# disarm_it_schem.net
KiCad netlist of a schematic drawn in Altium Designer
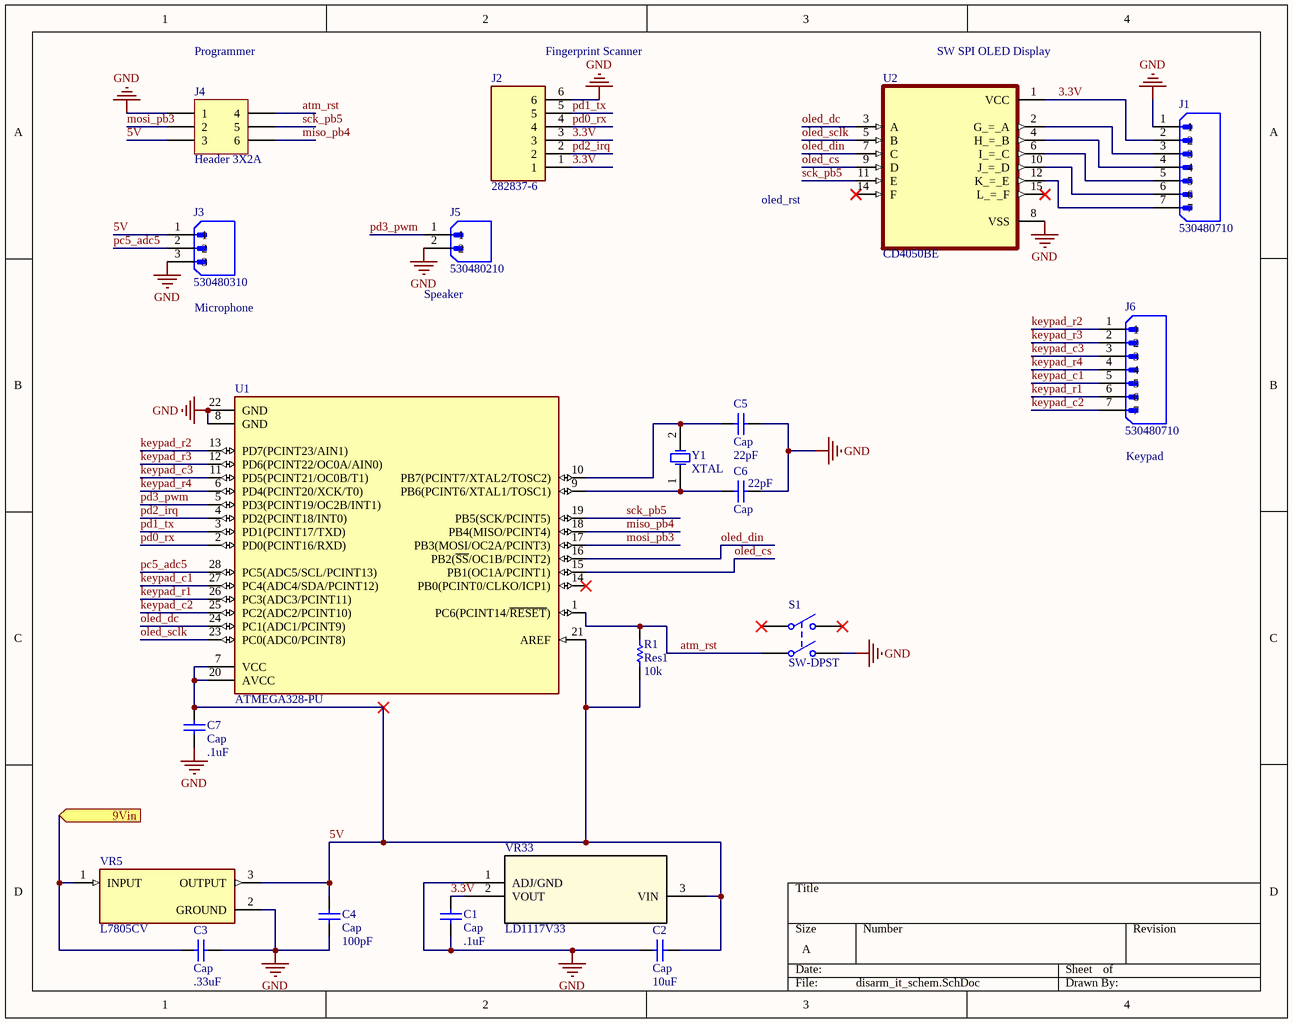
[diagram p0: disarm_it_schem.SchDoc]

(export (version "E")
  (design (tool "Eeschema 10.0.6"))
  (components
    (comp (ref "C1")
      (value "Cap")
      (footprint "RAD-0.3")
      (description "Capacitor")
      (fields (field (name "ALTIUM_VALUE") ".1uF") (field (name "PUBLISHER") "Altium Limited"))
      (libsource (lib "Miscellaneous Devices") (part "Cap"))
    )
    (comp (ref "C2")
      (value "Cap")
      (footprint "RAD-0.3")
      (description "Capacitor")
      (fields (field (name "ALTIUM_VALUE") "10uF") (field (name "PUBLISHER") "Altium Limited"))
      (libsource (lib "Miscellaneous Devices") (part "Cap"))
    )
    (comp (ref "C3")
      (value "Cap")
      (footprint "RAD-0.3")
      (description "Capacitor")
      (fields (field (name "ALTIUM_VALUE") ".33uF") (field (name "PUBLISHER") "Altium Limited"))
      (libsource (lib "Miscellaneous Devices") (part "Cap"))
    )
    (comp (ref "C4")
      (value "Cap")
      (footprint "RAD-0.3")
      (description "Capacitor")
      (fields (field (name "ALTIUM_VALUE") "100pF") (field (name "PUBLISHER") "Altium Limited"))
      (libsource (lib "Miscellaneous Devices") (part "Cap"))
    )
    (comp (ref "C5")
      (value "Cap")
      (footprint "RAD-0.3")
      (description "Capacitor")
      (fields (field (name "ALTIUM_VALUE") "22pF") (field (name "PUBLISHER") "Altium Limited"))
      (libsource (lib "Miscellaneous Devices") (part "Cap"))
    )
    (comp (ref "C6")
      (value "Cap")
      (footprint "RAD-0.3")
      (description "Capacitor")
      (fields (field (name "ALTIUM_VALUE") "22pF") (field (name "PUBLISHER") "Altium Limited"))
      (libsource (lib "Miscellaneous Devices") (part "Cap"))
    )
    (comp (ref "C7")
      (value "Cap")
      (footprint "RAD-0.3")
      (description "Capacitor")
      (fields (field (name "ALTIUM_VALUE") ".1uF") (field (name "PUBLISHER") "Altium Limited"))
      (libsource (lib "Miscellaneous Devices") (part "Cap"))
    )
    (comp (ref "J1")
      (value "530480710")
      (footprint "MOLEX_530480710")
      (libsource (lib "530480710") (part "530480710"))
    )
    (comp (ref "J2")
      (value "282837-6")
      (footprint "TE_282837-6")
      (description "Conn Terminal Block F 6 POS 5.08mm Solder ST Thru-Hole 13.5A/Contact")
      (fields (field (name "MF") "TE Connectivity"))
      (libsource (lib "282837-6") (part "282837-6"))
    )
    (comp (ref "J3")
      (value "530480310")
      (footprint "MOLEX_530480310")
      (description "Conn Shrouded Header (4 Sides) HDR 3 POS 1.25mm Solder RA Side Entry Thru-Hole PicoBladeâ„¢ Tray")
      (fields (field (name "MF") "Molex") (field (name "DIGI-KEY_PART_NUMBER") "2266-53048-0310-ND"))
      (libsource (lib "530480310") (part "530480310"))
    )
    (comp (ref "J4")
      (value "Header 3X2A")
      (footprint "HDR2X3_CEN")
      (description "Header, 3-Pin, Dual row")
      (fields (field (name "PUBLISHER") "Altium Limited"))
      (libsource (lib "Miscellaneous Connectors") (part "Header 3X2A"))
    )
    (comp (ref "J5")
      (value "530480210")
      (footprint "MOLEX_530480210")
      (description "Conn Shrouded Header (4 Sides) HDR 2 POS 1.25mm Solder RA Side Entry Thru-Hole PicoBladeâ„¢ Tray")
      (fields (field (name "MF") "Molex") (field (name "DIGI-KEY_PART_NUMBER") "2266-53048-0210-ND"))
      (libsource (lib "530480210") (part "530480210"))
    )
    (comp (ref "J6")
      (value "530480710")
      (footprint "MOLEX_530480710")
      (libsource (lib "530480710") (part "530480710"))
    )
    (comp (ref "R1")
      (value "Res1")
      (footprint "AXIAL-0.3")
      (description "Resistor")
      (fields (field (name "ALTIUM_VALUE") "10k") (field (name "PUBLISHER") "Altium Limited"))
      (libsource (lib "Miscellaneous Devices") (part "Res1"))
    )
    (comp (ref "S1")
      (value "SW-DPST")
      (footprint "DPST-4")
      (description "Double-Pole, Single-Throw Switch")
      (fields (field (name "PUBLISHER") "Altium Limited"))
      (libsource (lib "Miscellaneous Devices") (part "SW-DPST"))
    )
    (comp (ref "U1")
      (value "ATMEGA328-PU")
      (footprint "DIP787W46P254L3467H508Q28")
      (description "AVR AVRÂ® ATmega Microcontroller IC 8-Bit 20MHz 32KB (16K x 16) FLASH 28-PDIP")
      (fields (field (name "MF") "Microchip Technology"))
      (libsource (lib "ATMEGA328-PU") (part "ATMEGA328-PU"))
    )
    (comp (ref "U2")
      (value "CD4050BE")
      (footprint "DIP794W45P254L1969H508Q16")
      (description "CMOS Hex Non-Inverting Buffer/Converter 16-PDIP -55 to 125")
      (fields (field (name "MF") "Texas Instruments"))
      (libsource (lib "CD4050BE") (part "CD4050BE"))
    )
    (comp (ref "VR5")
      (value "L7805CV")
      (footprint "TO255P1040X460X1968-3")
      (description "Linear Voltage Regulator IC 1 Output 1.5A TO-220AB")
      (fields (field (name "MF") "STMicroelectronics"))
      (libsource (lib "L7805CV") (part "L7805CV"))
    )
    (comp (ref "VR33")
      (value "LD1117V33")
      (footprint "TO-220_STM")
      (description "No Description Available")
      (fields (field (name "COPYRIGHT") "Copyright (C) 2022 Ultra Librarian. All rights reserved."))
      (libsource (lib "LD1117V33") (part "LD1117V33"))
    )
    (comp (ref "Y1")
      (value "XTAL")
      (footprint "R38")
      (description "Crystal Oscillator")
      (fields (field (name "PUBLISHER") "Altium Limited"))
      (libsource (lib "Miscellaneous Devices") (part "XTAL"))
    )
  )
  (nets
    (net (code "1") (name "/3.3V") (class "Default")
      (node (ref "C1") (pin "2") (pinfunction "2_2") (pintype "passive"))
      (node (ref "J1") (pin "2") (pinfunction "2_2") (pintype "passive"))
      (node (ref "J2") (pin "1") (pinfunction "1_1") (pintype "passive"))
      (node (ref "J2") (pin "3") (pinfunction "3_3") (pintype "passive"))
      (node (ref "U2") (pin "1") (pinfunction "VCC_1") (pintype "power_in"))
      (node (ref "VR33") (pin "2") (pinfunction "VOUT_2") (pintype "power_in"))
    )
    (net (code "2") (name "/5V") (class "Default")
      (node (ref "C2") (pin "1") (pinfunction "1_1") (pintype "passive"))
      (node (ref "C4") (pin "1") (pinfunction "1_1") (pintype "passive"))
      (node (ref "C7") (pin "2") (pinfunction "2_2") (pintype "passive"))
      (node (ref "J3") (pin "1") (pinfunction "1_1") (pintype "passive"))
      (node (ref "J4") (pin "3") (pinfunction "3_3") (pintype "passive"))
      (node (ref "R1") (pin "1") (pinfunction "1_1") (pintype "passive"))
      (node (ref "U1") (pin "20") (pinfunction "AVCC_20") (pintype "power_in"))
      (node (ref "U1") (pin "21") (pinfunction "AREF_21") (pintype "input"))
      (node (ref "U1") (pin "7") (pinfunction "VCC_7") (pintype "power_in"))
      (node (ref "VR33") (pin "3") (pinfunction "VIN_3") (pintype "power_in"))
      (node (ref "VR5") (pin "3") (pinfunction "OUTPUT_3") (pintype "output"))
    )
    (net (code "3") (name "/9Vin") (class "Default")
      (node (ref "C3") (pin "1") (pinfunction "1_1") (pintype "passive"))
      (node (ref "VR5") (pin "1") (pinfunction "INPUT_1") (pintype "input"))
    )
    (net (code "4") (name "/atm_rst") (class "Default")
      (node (ref "J4") (pin "4") (pinfunction "4_4") (pintype "passive"))
      (node (ref "R1") (pin "2") (pinfunction "2_2") (pintype "passive"))
      (node (ref "S1") (pin "3") (pinfunction "COMMON2_3") (pintype "passive"))
      (node (ref "U1") (pin "1") (pinfunction "PC6(PCINT14/~{RESET})_1") (pintype "bidirectional"))
    )
    (net (code "5") (name "/keypad_c1") (class "Default")
      (node (ref "J6") (pin "5") (pinfunction "5_5") (pintype "passive"))
      (node (ref "U1") (pin "27") (pinfunction "PC4(ADC4/SDA/PCINT12)_27") (pintype "bidirectional"))
    )
    (net (code "6") (name "/keypad_c2") (class "Default")
      (node (ref "J6") (pin "7") (pinfunction "7_7") (pintype "passive"))
      (node (ref "U1") (pin "25") (pinfunction "PC2(ADC2/PCINT10)_25") (pintype "bidirectional"))
    )
    (net (code "7") (name "/keypad_c3") (class "Default")
      (node (ref "J6") (pin "3") (pinfunction "3_3") (pintype "passive"))
      (node (ref "U1") (pin "11") (pinfunction "PD5(PCINT21/OC0B/T1)_11") (pintype "bidirectional"))
    )
    (net (code "8") (name "/keypad_r1") (class "Default")
      (node (ref "J6") (pin "6") (pinfunction "6_6") (pintype "passive"))
      (node (ref "U1") (pin "26") (pinfunction "PC3(ADC3/PCINT11)_26") (pintype "bidirectional"))
    )
    (net (code "9") (name "/keypad_r2") (class "Default")
      (node (ref "J6") (pin "1") (pinfunction "1_1") (pintype "passive"))
      (node (ref "U1") (pin "13") (pinfunction "PD7(PCINT23/AIN1)_13") (pintype "bidirectional"))
    )
    (net (code "10") (name "/keypad_r3") (class "Default")
      (node (ref "J6") (pin "2") (pinfunction "2_2") (pintype "passive"))
      (node (ref "U1") (pin "12") (pinfunction "PD6(PCINT22/OC0A/AIN0)_12") (pintype "bidirectional"))
    )
    (net (code "11") (name "/keypad_r4") (class "Default")
      (node (ref "J6") (pin "4") (pinfunction "4_4") (pintype "passive"))
      (node (ref "U1") (pin "6") (pinfunction "PD4(PCINT20/XCK/T0)_6") (pintype "bidirectional"))
    )
    (net (code "12") (name "/miso_pb4") (class "Default")
      (node (ref "J4") (pin "6") (pinfunction "6_6") (pintype "passive"))
      (node (ref "U1") (pin "18") (pinfunction "PB4(MISO/PCINT4)_18") (pintype "bidirectional"))
    )
    (net (code "13") (name "/mosi_pb3") (class "Default")
      (node (ref "J4") (pin "2") (pinfunction "2_2") (pintype "passive"))
      (node (ref "U1") (pin "17") (pinfunction "PB3(MOSI/OC2A/PCINT3)_17") (pintype "bidirectional"))
    )
    (net (code "14") (name "/oled_cs") (class "Default")
      (node (ref "U1") (pin "15") (pinfunction "PB1(OC1A/PCINT1)_15") (pintype "bidirectional"))
      (node (ref "U2") (pin "9") (pinfunction "D_9") (pintype "input"))
    )
    (net (code "15") (name "/oled_dc") (class "Default")
      (node (ref "U1") (pin "24") (pinfunction "PC1(ADC1/PCINT9)_24") (pintype "bidirectional"))
      (node (ref "U2") (pin "3") (pinfunction "A_3") (pintype "input"))
    )
    (net (code "16") (name "/oled_din") (class "Default")
      (node (ref "U1") (pin "16") (pinfunction "PB2(~{SS}/OC1B/PCINT2)_16") (pintype "bidirectional"))
      (node (ref "U2") (pin "7") (pinfunction "C_7") (pintype "input"))
    )
    (net (code "17") (name "/oled_sclk") (class "Default")
      (node (ref "U1") (pin "23") (pinfunction "PC0(ADC0/PCINT8)_23") (pintype "bidirectional"))
      (node (ref "U2") (pin "5") (pinfunction "B_5") (pintype "input"))
    )
    (net (code "18") (name "/pc5_adc5") (class "Default")
      (node (ref "J3") (pin "2") (pinfunction "2_2") (pintype "passive"))
      (node (ref "U1") (pin "28") (pinfunction "PC5(ADC5/SCL/PCINT13)_28") (pintype "bidirectional"))
    )
    (net (code "19") (name "/pd0_rx") (class "Default")
      (node (ref "J2") (pin "4") (pinfunction "4_4") (pintype "passive"))
      (node (ref "U1") (pin "2") (pinfunction "PD0(PCINT16/RXD)_2") (pintype "bidirectional"))
    )
    (net (code "20") (name "/pd1_tx") (class "Default")
      (node (ref "J2") (pin "5") (pinfunction "5_5") (pintype "passive"))
      (node (ref "U1") (pin "3") (pinfunction "PD1(PCINT17/TXD)_3") (pintype "bidirectional"))
    )
    (net (code "21") (name "/pd2_irq") (class "Default")
      (node (ref "J2") (pin "2") (pinfunction "2_2") (pintype "passive"))
      (node (ref "U1") (pin "4") (pinfunction "PD2(PCINT18/INT0)_4") (pintype "bidirectional"))
    )
    (net (code "22") (name "/pd3_pwm") (class "Default")
      (node (ref "J5") (pin "1") (pinfunction "1_1") (pintype "passive"))
      (node (ref "U1") (pin "5") (pinfunction "PD3(PCINT19/OC2B/INT1)_5") (pintype "bidirectional"))
    )
    (net (code "23") (name "/sck_pb5") (class "Default")
      (node (ref "J4") (pin "5") (pinfunction "5_5") (pintype "passive"))
      (node (ref "U1") (pin "19") (pinfunction "PB5(SCK/PCINT5)_19") (pintype "bidirectional"))
      (node (ref "U2") (pin "11") (pinfunction "E_11") (pintype "input"))
    )
    (net (code "24") (name "GND") (class "Default")
      (node (ref "C1") (pin "1") (pinfunction "1_1") (pintype "passive"))
      (node (ref "C2") (pin "2") (pinfunction "2_2") (pintype "passive"))
      (node (ref "C3") (pin "2") (pinfunction "2_2") (pintype "passive"))
      (node (ref "C4") (pin "2") (pinfunction "2_2") (pintype "passive"))
      (node (ref "C5") (pin "2") (pinfunction "2_2") (pintype "passive"))
      (node (ref "C6") (pin "2") (pinfunction "2_2") (pintype "passive"))
      (node (ref "C7") (pin "1") (pinfunction "1_1") (pintype "passive"))
      (node (ref "J1") (pin "1") (pinfunction "1_1") (pintype "passive"))
      (node (ref "J2") (pin "6") (pinfunction "6_6") (pintype "passive"))
      (node (ref "J3") (pin "3") (pinfunction "3_3") (pintype "passive"))
      (node (ref "J4") (pin "1") (pinfunction "1_1") (pintype "passive"))
      (node (ref "J5") (pin "2") (pinfunction "2_2") (pintype "passive"))
      (node (ref "S1") (pin "4") (pinfunction "NO2_4") (pintype "passive"))
      (node (ref "U1") (pin "22") (pinfunction "GND_22") (pintype "power_in"))
      (node (ref "U1") (pin "8") (pinfunction "GND_8") (pintype "power_in"))
      (node (ref "U2") (pin "8") (pinfunction "VSS_8") (pintype "power_in"))
      (node (ref "VR33") (pin "1") (pinfunction "ADJ/GND_1") (pintype "passive"))
      (node (ref "VR5") (pin "2") (pinfunction "GROUND_2") (pintype "power_in"))
    )
    (net (code "25") (name "Net-(U1-PB6(PCINT6{slash}XTAL1{slash}TOSC1))") (class "Default")
      (node (ref "C6") (pin "1") (pinfunction "1_1") (pintype "passive"))
      (node (ref "U1") (pin "9") (pinfunction "PB6(PCINT6/XTAL1/TOSC1)_9") (pintype "bidirectional"))
      (node (ref "Y1") (pin "1") (pinfunction "OSC1_1") (pintype "passive"))
    )
    (net (code "26") (name "Net-(U1-PB7(PCINT7{slash}XTAL2{slash}TOSC2))") (class "Default")
      (node (ref "C5") (pin "1") (pinfunction "1_1") (pintype "passive"))
      (node (ref "U1") (pin "10") (pinfunction "PB7(PCINT7/XTAL2/TOSC2)_10") (pintype "bidirectional"))
      (node (ref "Y1") (pin "2") (pinfunction "OSC2_2") (pintype "passive"))
    )
    (net (code "27") (name "Net-(U2-G_=_A)") (class "Default")
      (node (ref "J1") (pin "3") (pinfunction "3_3") (pintype "passive"))
      (node (ref "U2") (pin "2") (pinfunction "G_=_A_2") (pintype "output"))
    )
    (net (code "28") (name "Net-(U2-H_=_B)") (class "Default")
      (node (ref "J1") (pin "4") (pinfunction "4_4") (pintype "passive"))
      (node (ref "U2") (pin "4") (pinfunction "H_=_B_4") (pintype "output"))
    )
    (net (code "29") (name "Net-(U2-I_=_C)") (class "Default")
      (node (ref "J1") (pin "5") (pinfunction "5_5") (pintype "passive"))
      (node (ref "U2") (pin "6") (pinfunction "I_=_C_6") (pintype "output"))
    )
    (net (code "30") (name "Net-(U2-J_=_D)") (class "Default")
      (node (ref "J1") (pin "6") (pinfunction "6_6") (pintype "passive"))
      (node (ref "U2") (pin "10") (pinfunction "J_=_D_10") (pintype "output"))
    )
    (net (code "31") (name "Net-(U2-K_=_E)") (class "Default")
      (node (ref "J1") (pin "7") (pinfunction "7_7") (pintype "passive"))
      (node (ref "U2") (pin "12") (pinfunction "K_=_E_12") (pintype "output"))
    )
    (net (code "32") (name "unconnected-(S1-COMMON1-Pad1)") (class "Default")
      (node (ref "S1") (pin "1") (pinfunction "COMMON1_1") (pintype "passive+no_connect"))
    )
    (net (code "33") (name "unconnected-(S1-NO1-Pad2)") (class "Default")
      (node (ref "S1") (pin "2") (pinfunction "NO1_2") (pintype "passive+no_connect"))
    )
    (net (code "34") (name "unconnected-(U1-PB0(PCINT0{slash}CLKO{slash}ICP1)-Pad14)") (class "Default")
      (node (ref "U1") (pin "14") (pinfunction "PB0(PCINT0/CLKO/ICP1)_14") (pintype "bidirectional+no_connect"))
    )
    (net (code "35") (name "unconnected-(U2-F-Pad14)") (class "Default")
      (node (ref "U2") (pin "14") (pinfunction "F_14") (pintype "input+no_connect"))
    )
    (net (code "36") (name "unconnected-(U2-L_=_F-Pad15)") (class "Default")
      (node (ref "U2") (pin "15") (pinfunction "L_=_F_15") (pintype "output+no_connect"))
    )
  )
)
